# MainSheet.net
KiCad netlist of a schematic drawn in Altium Designer
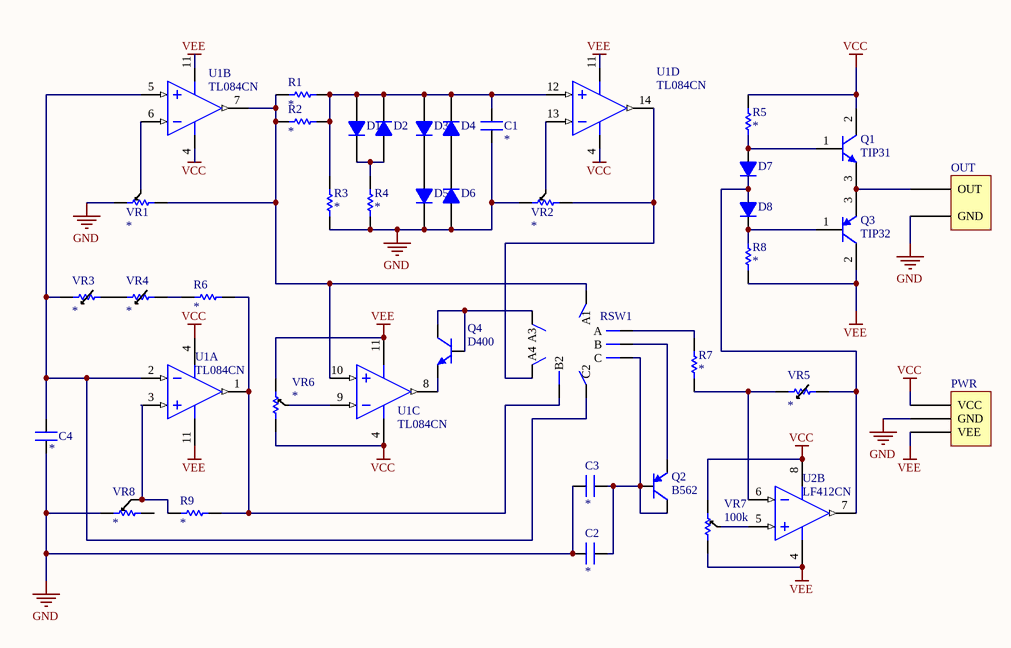
[diagram p0: MainSheet.SchDoc]

(export (version "E")
  (design (tool "Eeschema 10.0.6"))
  (components
    (comp (ref "C1")
      (value "Cap3")
      (footprint "CAP3")
      (description "Capacitor")
      (fields (field (name "ALTIUM_VALUE") "*") (field (name "PUBLISHER") "Altium Limited"))
      (libsource (lib "Common Parts") (part "Cap3"))
    )
    (comp (ref "C2")
      (value "Cap3")
      (footprint "CAP4(200mil)")
      (description "Capacitor")
      (fields (field (name "ALTIUM_VALUE") "*") (field (name "PUBLISHER") "Altium Limited"))
      (libsource (lib "Common Parts") (part "Cap3"))
    )
    (comp (ref "C3")
      (value "Cap3")
      (footprint "CAP4(200mil)")
      (description "Capacitor")
      (fields (field (name "ALTIUM_VALUE") "*") (field (name "PUBLISHER") "Altium Limited"))
      (libsource (lib "Common Parts") (part "Cap3"))
    )
    (comp (ref "C4")
      (value "Cap3")
      (footprint "CAP4(200mil)")
      (description "Capacitor")
      (fields (field (name "ALTIUM_VALUE") "*") (field (name "PUBLISHER") "Altium Limited"))
      (libsource (lib "Common Parts") (part "Cap3"))
    )
    (comp (ref "D1")
      (value "1N4007")
      (footprint "1N4007")
      (description "1 Amp General Purpose Rectifier")
      (fields (field (name "PUBLISHER") "Altium Limited"))
      (libsource (lib "Common Parts") (part "1N4007"))
    )
    (comp (ref "D2")
      (value "1N4007")
      (footprint "1N4007")
      (description "1 Amp General Purpose Rectifier")
      (fields (field (name "PUBLISHER") "Altium Limited"))
      (libsource (lib "Common Parts") (part "1N4007"))
    )
    (comp (ref "D3")
      (value "1N4007")
      (footprint "1N4007")
      (description "1 Amp General Purpose Rectifier")
      (fields (field (name "PUBLISHER") "Altium Limited"))
      (libsource (lib "Common Parts") (part "1N4007"))
    )
    (comp (ref "D4")
      (value "1N4007")
      (footprint "1N4007")
      (description "1 Amp General Purpose Rectifier")
      (fields (field (name "PUBLISHER") "Altium Limited"))
      (libsource (lib "Common Parts") (part "1N4007"))
    )
    (comp (ref "D5")
      (value "1N4007")
      (footprint "1N4007")
      (description "1 Amp General Purpose Rectifier")
      (fields (field (name "PUBLISHER") "Altium Limited"))
      (libsource (lib "Common Parts") (part "1N4007"))
    )
    (comp (ref "D6")
      (value "1N4007")
      (footprint "1N4007")
      (description "1 Amp General Purpose Rectifier")
      (fields (field (name "PUBLISHER") "Altium Limited"))
      (libsource (lib "Common Parts") (part "1N4007"))
    )
    (comp (ref "D7")
      (value "1N4007")
      (footprint "1N4007")
      (description "1 Amp General Purpose Rectifier")
      (fields (field (name "PUBLISHER") "Altium Limited"))
      (libsource (lib "Common Parts") (part "1N4007"))
    )
    (comp (ref "D8")
      (value "1N4007")
      (footprint "1N4007")
      (description "1 Amp General Purpose Rectifier")
      (fields (field (name "PUBLISHER") "Altium Limited"))
      (libsource (lib "Common Parts") (part "1N4007"))
    )
    (comp (ref "OUT") (value "SigOut") (footprint "PWR2") (libsource (lib "Common Parts") (part "SigOut")))
    (comp (ref "PWR") (value "PWR3") (footprint "PWR3") (libsource (lib "Common Parts") (part "PWR3")))
    (comp (ref "Q1")
      (value "TIP31")
      (footprint "ONSC-TO-220-3-221A-09")
      (description "Complementary Silicon Plastic Power Transistor, 3-Pin TO-220, Tube")
      (fields (field (name "MANUFACTURER") "On Semiconductor"))
      (libsource (lib "Altium Content Vault") (part "ONSC-NPN-B1C2E3-3_C"))
    )
    (comp (ref "Q2")
      (value "B562")
      (footprint "TO-92_ONS")
      (description "PNP General Purpose Transistor")
      (fields (field (name "PUBLISHER") "Altium Limited"))
      (libsource (lib "Common Parts") (part "A733"))
    )
    (comp (ref "Q3")
      (value "TIP32")
      (footprint "ONSC-TO-220-3-221A-09")
      (description "Complementary Silicon Plastic Power Transistor, 3-Pin TO-220, Tube")
      (fields (field (name "MANUFACTURER") "On Semiconductor"))
      (libsource (lib "Altium Content Vault") (part "ONSC-PNP-B1C2E3-3"))
    )
    (comp (ref "Q4")
      (value "D400")
      (footprint "TO-92_ONS")
      (description "NPN General Purpose Transistor")
      (fields (field (name "PUBLISHER") "Altium Limited"))
      (libsource (lib "Common Parts") (part "C828"))
    )
    (comp (ref "R1")
      (value "Res1")
      (footprint "RES")
      (description "Resistor")
      (fields (field (name "ALTIUM_VALUE") "*") (field (name "PUBLISHER") "Altium Limited"))
      (libsource (lib "Common Parts") (part "Res1"))
    )
    (comp (ref "R2")
      (value "Res1")
      (footprint "RES")
      (description "Resistor")
      (fields (field (name "ALTIUM_VALUE") "*") (field (name "PUBLISHER") "Altium Limited"))
      (libsource (lib "Common Parts") (part "Res1"))
    )
    (comp (ref "R3")
      (value "Res1")
      (footprint "RES")
      (description "Resistor")
      (fields (field (name "ALTIUM_VALUE") "*") (field (name "PUBLISHER") "Altium Limited"))
      (libsource (lib "Common Parts") (part "Res1"))
    )
    (comp (ref "R4")
      (value "Res1")
      (footprint "RES")
      (description "Resistor")
      (fields (field (name "ALTIUM_VALUE") "*") (field (name "PUBLISHER") "Altium Limited"))
      (libsource (lib "Common Parts") (part "Res1"))
    )
    (comp (ref "R5")
      (value "Res1")
      (footprint "RES")
      (description "Resistor")
      (fields (field (name "ALTIUM_VALUE") "*") (field (name "PUBLISHER") "Altium Limited"))
      (libsource (lib "Common Parts") (part "Res1"))
    )
    (comp (ref "R6")
      (value "Res1")
      (footprint "RES")
      (description "Resistor")
      (fields (field (name "ALTIUM_VALUE") "*") (field (name "PUBLISHER") "Altium Limited"))
      (libsource (lib "Common Parts") (part "Res1"))
    )
    (comp (ref "R7")
      (value "Res1")
      (footprint "RES")
      (description "Resistor")
      (fields (field (name "ALTIUM_VALUE") "*") (field (name "PUBLISHER") "Altium Limited"))
      (libsource (lib "Common Parts") (part "Res1"))
    )
    (comp (ref "R8")
      (value "Res1")
      (footprint "RES")
      (description "Resistor")
      (fields (field (name "ALTIUM_VALUE") "*") (field (name "PUBLISHER") "Altium Limited"))
      (libsource (lib "Common Parts") (part "Res1"))
    )
    (comp (ref "R9")
      (value "Res1")
      (footprint "RES")
      (description "Resistor")
      (fields (field (name "ALTIUM_VALUE") "*") (field (name "PUBLISHER") "Altium Limited"))
      (libsource (lib "Common Parts") (part "Res1"))
    )
    (comp (ref "RSW1")
      (value "RotarySwitch")
      (footprint "ROTARY_SWITCH")
      (libsource (lib "Integrated_Library_Rotary") (part "RotarySwitch"))
    )
    (comp (ref "U1")
      (value "TL084CN")
      (footprint "N0014A")
      (description "JFET-Input Operational Amplifier, 7 to 36 V, 0 to 70 degC, 14-pin DIP (N14), Pb-Free (RoHS)")
      (fields (field (name "MANUFACTURER") "Texas Instruments"))
      (libsource (lib "Altium Content Vault") (part "TI-TLXX4X_MC3403-X14"))
    )
    (comp (ref "U2")
      (value "LF412CN")
      (footprint "N08E")
      (description "Low Offset, Low Drift Dual JFET Input Operational Amplifier, 8-pin MDIP")
      (fields (field (name "MANUFACTURER") "National Semiconductor"))
      (libsource (lib "Altium Content Vault") (part "AMP-OPA-LF353-8"))
    )
    (comp (ref "VR1")
      (value "VR3")
      (footprint "VR_PRESET")
      (fields (field (name "ALTIUM_VALUE") "*"))
      (libsource (lib "Common Parts") (part "VR3"))
    )
    (comp (ref "VR2")
      (value "VR3")
      (footprint "VR_PRESET")
      (fields (field (name "ALTIUM_VALUE") "*"))
      (libsource (lib "Common Parts") (part "VR3"))
    )
    (comp (ref "VR3")
      (value "VR2_2PIN")
      (footprint "VR_VOL_CTRL_2")
      (fields (field (name "ALTIUM_VALUE") "*"))
      (libsource (lib "Common Parts") (part "VR2_2PIN"))
    )
    (comp (ref "VR4")
      (value "VR2_2PIN")
      (footprint "VR_VOL_CTRL_2")
      (fields (field (name "ALTIUM_VALUE") "*"))
      (libsource (lib "Common Parts") (part "VR2_2PIN"))
    )
    (comp (ref "VR5")
      (value "VR2_2PIN")
      (footprint "VR_VOL_CTRL_2")
      (fields (field (name "ALTIUM_VALUE") "*"))
      (libsource (lib "Common Parts") (part "VR2_2PIN"))
    )
    (comp (ref "VR6")
      (value "VR3")
      (footprint "VR_VOL_CTRL")
      (fields (field (name "ALTIUM_VALUE") "*"))
      (libsource (lib "Common Parts") (part "VR3"))
    )
    (comp (ref "VR7")
      (value "100k")
      (footprint "VR_VOL_CTRL")
      (fields (field (name "Comment") "VR7"))
      (libsource (lib "Common Parts") (part "VR3"))
    )
    (comp (ref "VR8")
      (value "VR2")
      (footprint "VR_PRESET")
      (fields (field (name "ALTIUM_VALUE") "*"))
      (libsource (lib "Common Parts") (part "VR2"))
    )
  )
  (nets
    (net (code "1") (name "GND") (class "Default")
      (node (ref "C1") (pin "1") (pinfunction "1_1") (pintype "passive"))
      (node (ref "C2") (pin "2") (pinfunction "2_2") (pintype "passive"))
      (node (ref "C3") (pin "2") (pinfunction "2_2") (pintype "passive"))
      (node (ref "C4") (pin "1") (pinfunction "1_1") (pintype "passive"))
      (node (ref "D5") (pin "2") (pinfunction "K_2") (pintype "passive"))
      (node (ref "D6") (pin "1") (pinfunction "A_1") (pintype "passive"))
      (node (ref "OUT") (pin "2") (pinfunction "GND_2") (pintype "passive"))
      (node (ref "PWR") (pin "2") (pinfunction "GND_2") (pintype "passive"))
      (node (ref "R3") (pin "1") (pinfunction "1_1") (pintype "passive"))
      (node (ref "R4") (pin "1") (pinfunction "1_1") (pintype "passive"))
      (node (ref "VR1") (pin "2") (pinfunction "2_2") (pintype "passive"))
      (node (ref "VR2") (pin "2") (pinfunction "2_2") (pintype "passive"))
      (node (ref "VR8") (pin "2") (pinfunction "2_2") (pintype "passive"))
    )
    (net (code "2") (name "Net-(D1-A)") (class "Default")
      (node (ref "C1") (pin "2") (pinfunction "2_2") (pintype "passive"))
      (node (ref "D1") (pin "1") (pinfunction "A_1") (pintype "passive"))
      (node (ref "D2") (pin "2") (pinfunction "K_2") (pintype "passive"))
      (node (ref "D3") (pin "1") (pinfunction "A_1") (pintype "passive"))
      (node (ref "D4") (pin "2") (pinfunction "K_2") (pintype "passive"))
      (node (ref "R1") (pin "2") (pinfunction "2_2") (pintype "passive"))
      (node (ref "R2") (pin "2") (pinfunction "2_2") (pintype "passive"))
      (node (ref "R3") (pin "2") (pinfunction "2_2") (pintype "passive"))
      (node (ref "U1") (pin "12") (pinfunction "IN4+_12") (pintype "input"))
    )
    (net (code "3") (name "Net-(D1-K)") (class "Default")
      (node (ref "D1") (pin "2") (pinfunction "K_2") (pintype "passive"))
      (node (ref "D2") (pin "1") (pinfunction "A_1") (pintype "passive"))
      (node (ref "R4") (pin "2") (pinfunction "2_2") (pintype "passive"))
    )
    (net (code "4") (name "Net-(D3-K)") (class "Default")
      (node (ref "D3") (pin "2") (pinfunction "K_2") (pintype "passive"))
      (node (ref "D5") (pin "1") (pinfunction "A_1") (pintype "passive"))
    )
    (net (code "5") (name "Net-(D4-A)") (class "Default")
      (node (ref "D4") (pin "1") (pinfunction "A_1") (pintype "passive"))
      (node (ref "D6") (pin "2") (pinfunction "K_2") (pintype "passive"))
    )
    (net (code "6") (name "Net-(D7-A)") (class "Default")
      (node (ref "D7") (pin "1") (pinfunction "A_1") (pintype "passive"))
      (node (ref "Q1") (pin "1") (pinfunction "B_1") (pintype "passive"))
      (node (ref "R5") (pin "1") (pinfunction "1_1") (pintype "passive"))
    )
    (net (code "7") (name "Net-(D7-K)") (class "Default")
      (node (ref "D7") (pin "2") (pinfunction "K_2") (pintype "passive"))
      (node (ref "D8") (pin "1") (pinfunction "A_1") (pintype "passive"))
      (node (ref "U2") (pin "7") (pinfunction "OUTB_7") (pintype "output"))
      (node (ref "VR5") (pin "2") (pinfunction "2_2") (pintype "passive"))
    )
    (net (code "8") (name "Net-(D8-K)") (class "Default")
      (node (ref "D8") (pin "2") (pinfunction "K_2") (pintype "passive"))
      (node (ref "Q3") (pin "1") (pinfunction "B_1") (pintype "passive"))
      (node (ref "R8") (pin "2") (pinfunction "2_2") (pintype "passive"))
    )
    (net (code "9") (name "Net-(OUT-OUT)") (class "Default")
      (node (ref "OUT") (pin "1") (pinfunction "OUT_1") (pintype "passive"))
      (node (ref "Q1") (pin "3") (pinfunction "E_3") (pintype "passive"))
      (node (ref "Q3") (pin "3") (pinfunction "E_3") (pintype "passive"))
    )
    (net (code "10") (name "Net-(Q2-B)") (class "Default")
      (node (ref "C2") (pin "1") (pinfunction "1_1") (pintype "passive"))
      (node (ref "C3") (pin "1") (pinfunction "1_1") (pintype "passive"))
      (node (ref "Q2") (pin "2") (pinfunction "C_2") (pintype "passive"))
      (node (ref "Q2") (pin "3") (pinfunction "B_3") (pintype "passive"))
      (node (ref "RSW1") (pin "C") (pinfunction "C_C") (pintype "passive"))
    )
    (net (code "11") (name "Net-(Q2-E)") (class "Default")
      (node (ref "Q2") (pin "1") (pinfunction "E_1") (pintype "passive"))
      (node (ref "RSW1") (pin "B") (pinfunction "B_B") (pintype "passive"))
    )
    (net (code "12") (name "Net-(Q4-B)") (class "Default")
      (node (ref "Q4") (pin "2") (pinfunction "C_2") (pintype "passive"))
      (node (ref "Q4") (pin "3") (pinfunction "B_3") (pintype "passive"))
      (node (ref "RSW1") (pin "A3") (pinfunction "A3_A3") (pintype "passive"))
    )
    (net (code "13") (name "Net-(Q4-E)") (class "Default")
      (node (ref "Q4") (pin "1") (pinfunction "E_1") (pintype "passive"))
      (node (ref "U1") (pin "8") (pinfunction "OUT3_8") (pintype "output"))
    )
    (net (code "14") (name "Net-(R6-Pad1)") (class "Default")
      (node (ref "R6") (pin "1") (pinfunction "1_1") (pintype "passive"))
      (node (ref "VR4") (pin "2") (pinfunction "2_2") (pintype "passive"))
    )
    (net (code "15") (name "Net-(R7-Pad2)") (class "Default")
      (node (ref "R7") (pin "2") (pinfunction "2_2") (pintype "passive"))
      (node (ref "RSW1") (pin "A") (pinfunction "A_A") (pintype "passive"))
    )
    (net (code "16") (name "Net-(U1A-IN1+)") (class "Default")
      (node (ref "R9") (pin "1") (pinfunction "1_1") (pintype "passive"))
      (node (ref "U1") (pin "3") (pinfunction "IN1+_3") (pintype "input"))
      (node (ref "VR8") (pin "1") (pinfunction "1_1") (pintype "passive"))
    )
    (net (code "17") (name "Net-(U1A-IN1-)") (class "Default")
      (node (ref "C4") (pin "2") (pinfunction "2_2") (pintype "passive"))
      (node (ref "RSW1") (pin "C2") (pinfunction "C2_C2") (pintype "passive"))
      (node (ref "U1") (pin "2") (pinfunction "IN1-_2") (pintype "input"))
      (node (ref "U1") (pin "5") (pinfunction "IN2+_5") (pintype "input"))
      (node (ref "VR3") (pin "1") (pinfunction "1_1") (pintype "passive"))
    )
    (net (code "18") (name "Net-(U1A-OUT1)") (class "Default")
      (node (ref "R6") (pin "2") (pinfunction "2_2") (pintype "passive"))
      (node (ref "R9") (pin "2") (pinfunction "2_2") (pintype "passive"))
      (node (ref "RSW1") (pin "B2") (pinfunction "B2_B2") (pintype "passive"))
      (node (ref "U1") (pin "1") (pinfunction "OUT1_1") (pintype "output"))
    )
    (net (code "19") (name "Net-(U1B-IN2-)") (class "Default")
      (node (ref "U1") (pin "6") (pinfunction "IN2-_6") (pintype "input"))
      (node (ref "VR1") (pin "1") (pinfunction "1_1") (pintype "passive"))
    )
    (net (code "20") (name "Net-(U1B-OUT2)") (class "Default")
      (node (ref "R1") (pin "1") (pinfunction "1_1") (pintype "passive"))
      (node (ref "R2") (pin "1") (pinfunction "1_1") (pintype "passive"))
      (node (ref "RSW1") (pin "A1") (pinfunction "A1_A1") (pintype "passive"))
      (node (ref "U1") (pin "10") (pinfunction "IN3+_10") (pintype "input"))
      (node (ref "U1") (pin "7") (pinfunction "OUT2_7") (pintype "output"))
      (node (ref "VR1") (pin "3") (pinfunction "3_3") (pintype "passive"))
    )
    (net (code "21") (name "Net-(U1C-IN3-)") (class "Default")
      (node (ref "U1") (pin "9") (pinfunction "IN3-_9") (pintype "input"))
      (node (ref "VR6") (pin "1") (pinfunction "1_1") (pintype "passive"))
    )
    (net (code "22") (name "Net-(U1D-IN4-)") (class "Default")
      (node (ref "U1") (pin "13") (pinfunction "IN4-_13") (pintype "input"))
      (node (ref "VR2") (pin "1") (pinfunction "1_1") (pintype "passive"))
    )
    (net (code "23") (name "Net-(U1D-OUT4)") (class "Default")
      (node (ref "RSW1") (pin "A4") (pinfunction "A4_A4") (pintype "passive"))
      (node (ref "U1") (pin "14") (pinfunction "OUT4_14") (pintype "output"))
      (node (ref "VR2") (pin "3") (pinfunction "3_3") (pintype "passive"))
    )
    (net (code "24") (name "Net-(U2B-INB+)") (class "Default")
      (node (ref "U2") (pin "5") (pinfunction "INB+_5") (pintype "input"))
      (node (ref "VR7") (pin "1") (pinfunction "1_1") (pintype "passive"))
    )
    (net (code "25") (name "Net-(U2B-INB-)") (class "Default")
      (node (ref "R7") (pin "1") (pinfunction "1_1") (pintype "passive"))
      (node (ref "U2") (pin "6") (pinfunction "INB-_6") (pintype "input"))
      (node (ref "VR5") (pin "1") (pinfunction "1_1") (pintype "passive"))
    )
    (net (code "26") (name "Net-(VR3-Pad2)") (class "Default")
      (node (ref "VR3") (pin "2") (pinfunction "2_2") (pintype "passive"))
      (node (ref "VR4") (pin "1") (pinfunction "1_1") (pintype "passive"))
    )
    (net (code "27") (name "VCC") (class "Default")
      (node (ref "PWR") (pin "1") (pinfunction "VCC_1") (pintype "passive"))
      (node (ref "Q1") (pin "2") (pinfunction "C_2") (pintype "passive"))
      (node (ref "R5") (pin "2") (pinfunction "2_2") (pintype "passive"))
      (node (ref "U1") (pin "4") (pinfunction "VCC+_4") (pintype "power_in"))
      (node (ref "U2") (pin "8") (pinfunction "V+_8") (pintype "power_in"))
      (node (ref "VR6") (pin "3") (pinfunction "3_3") (pintype "passive"))
      (node (ref "VR7") (pin "2") (pinfunction "2_2") (pintype "passive"))
    )
    (net (code "28") (name "VEE") (class "Default")
      (node (ref "PWR") (pin "3") (pinfunction "VEE_3") (pintype "passive"))
      (node (ref "Q3") (pin "2") (pinfunction "C_2") (pintype "passive"))
      (node (ref "R8") (pin "1") (pinfunction "1_1") (pintype "passive"))
      (node (ref "U1") (pin "11") (pinfunction "VCC-_11") (pintype "power_in"))
      (node (ref "U2") (pin "4") (pinfunction "V-_4") (pintype "power_in"))
      (node (ref "VR6") (pin "2") (pinfunction "2_2") (pintype "passive"))
      (node (ref "VR7") (pin "3") (pinfunction "3_3") (pintype "passive"))
    )
    (net (code "29") (name "unconnected-(VR8-Pad3)") (class "Default")
      (node (ref "VR8") (pin "3") (pinfunction "3_3") (pintype "passive"))
    )
  )
)
